# project_Sheet.net
KiCad netlist of a schematic drawn in Altium Designer
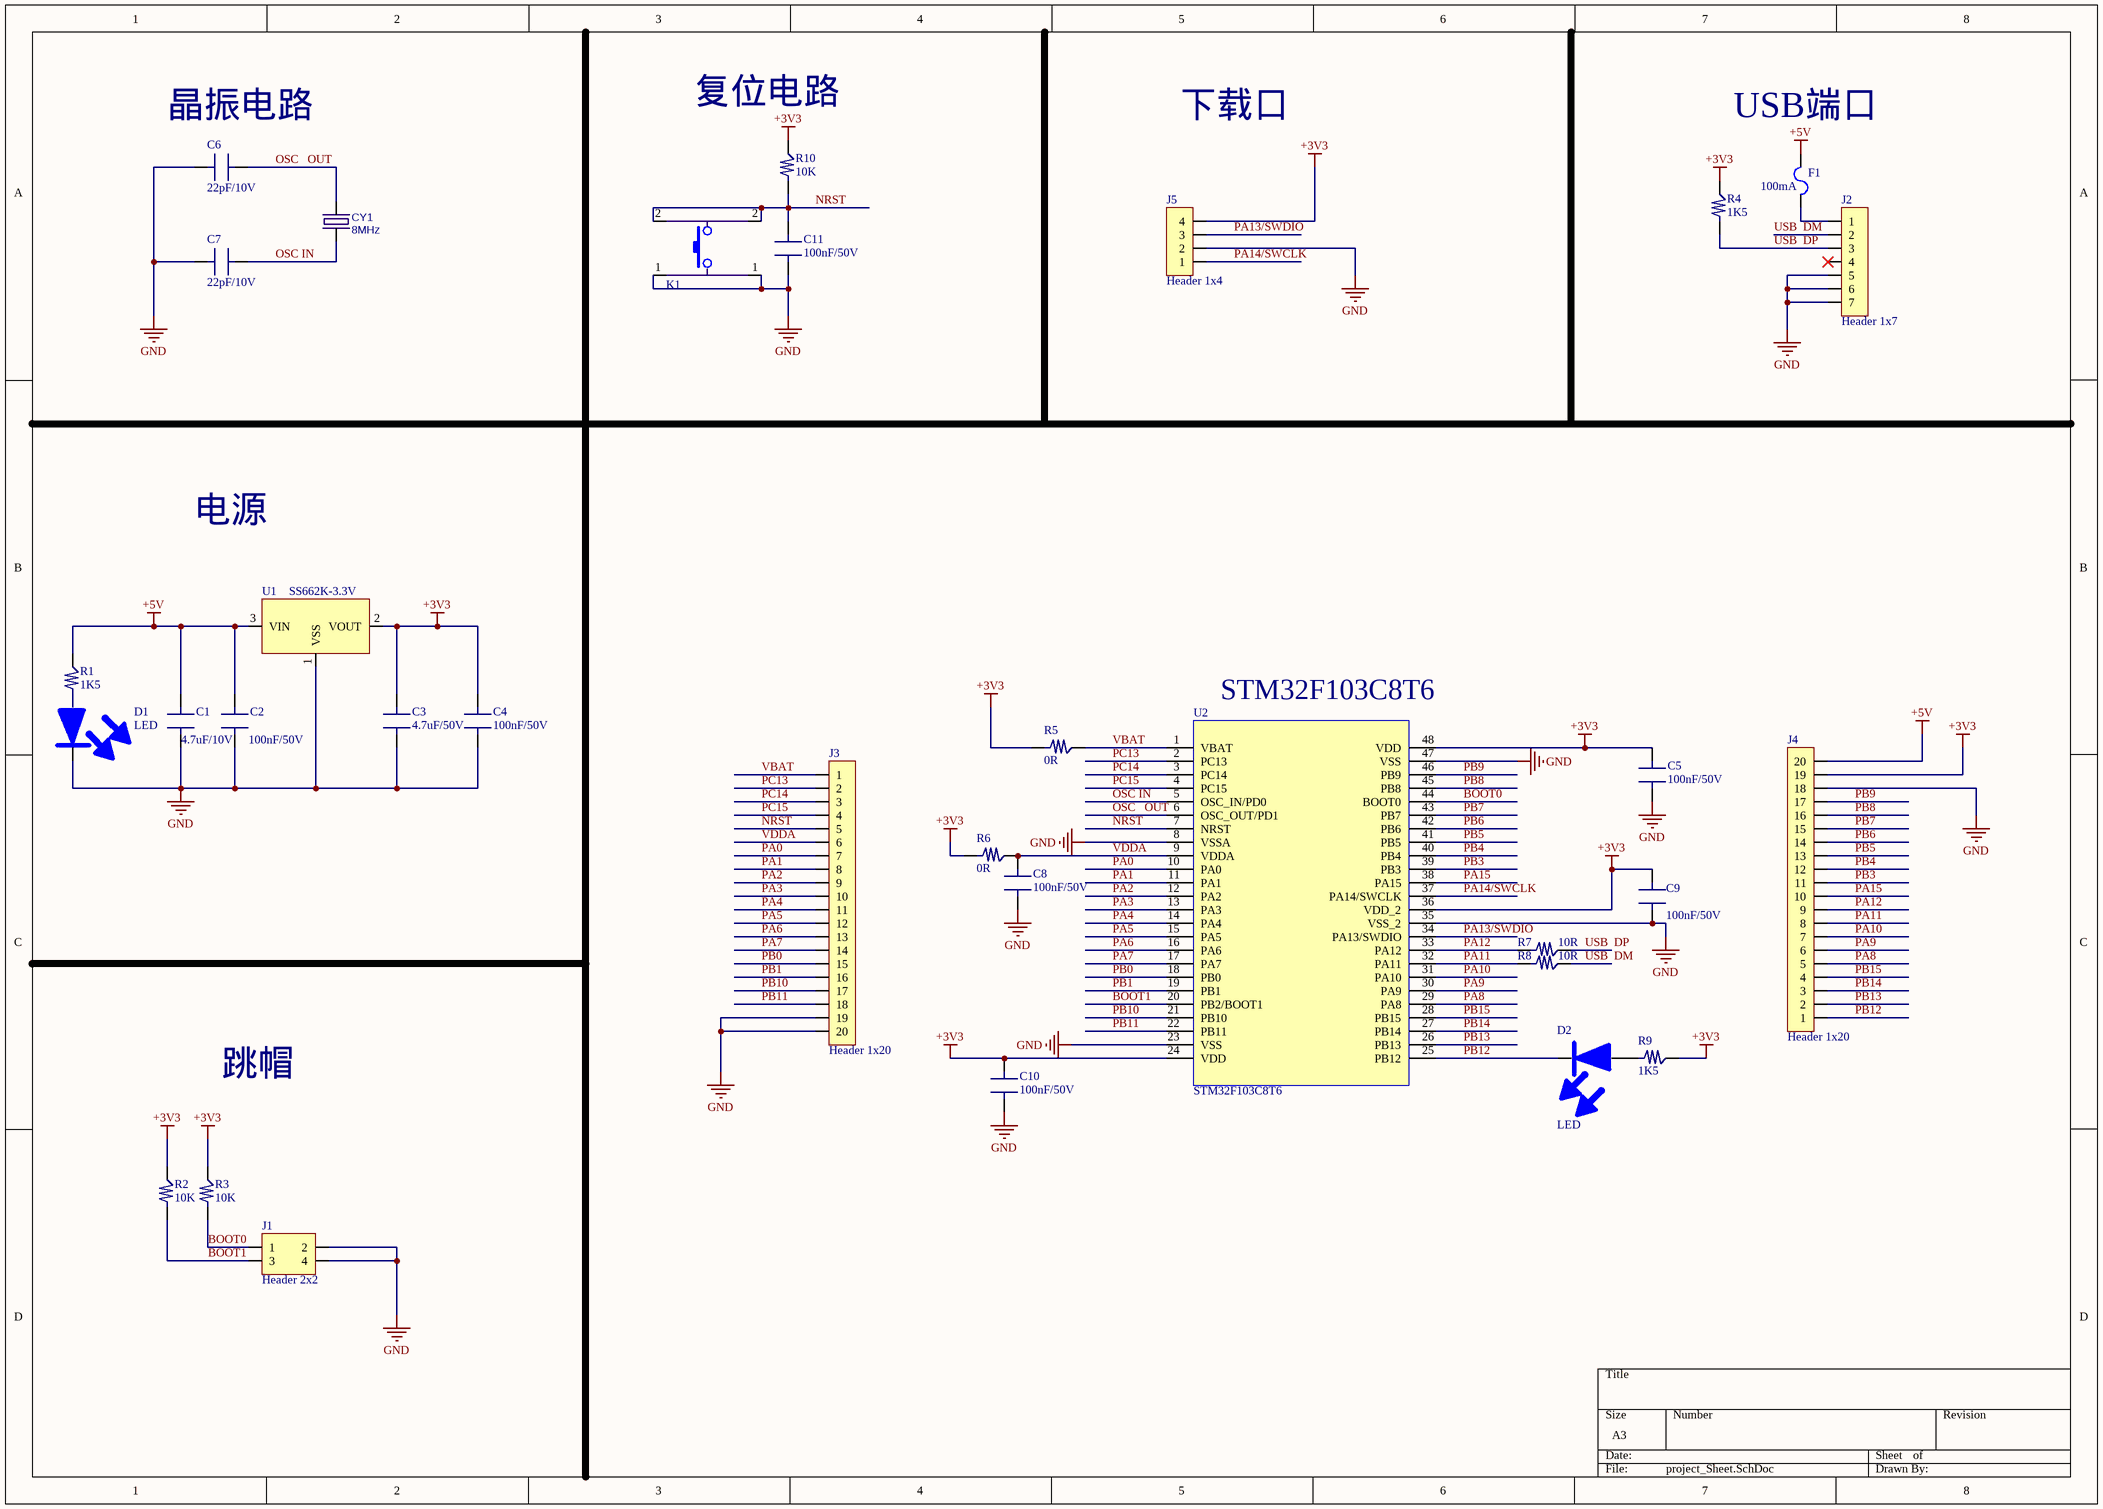
[diagram p0: project_Sheet.SchDoc]

(export (version "E")
  (design (tool "Eeschema 10.0.6"))
  (components
    (comp (ref "C1") (value "4.7uF/10V") (footprint "0603CC") (libsource (lib "F1A") (part "CAP")))
    (comp (ref "C2") (value "100nF/50V") (footprint "0603CC") (libsource (lib "F1A") (part "CAP")))
    (comp (ref "C3") (value "4.7uF/50V") (footprint "0805CC") (libsource (lib "F1A") (part "CAP")))
    (comp (ref "C4") (value "100nF/50V") (footprint "0805CC") (libsource (lib "F1A") (part "CAP")))
    (comp (ref "C5") (value "100nF/50V") (footprint "0603CC") (libsource (lib "F1A") (part "CAP")))
    (comp (ref "C6") (value "22pF/10V") (footprint "0603CC") (libsource (lib "F1A") (part "CAP")))
    (comp (ref "C7") (value "22pF/10V") (footprint "0603CC") (libsource (lib "F1A") (part "CAP")))
    (comp (ref "C8") (value "100nF/50V") (footprint "0603CC") (libsource (lib "F1A") (part "CAP")))
    (comp (ref "C9") (value "100nF/50V") (footprint "0603CC") (libsource (lib "F1A") (part "CAP")))
    (comp (ref "C10") (value "100nF/50V") (footprint "0603CC") (libsource (lib "F1A") (part "CAP")))
    (comp (ref "C11") (value "100nF/50V") (footprint "0603CC") (libsource (lib "F1A") (part "CAP")))
    (comp (ref "CY1")
      (value "8MHz")
      (footprint "HC-49S")
      (description "2pin晶振")
      (libsource (lib "F1A") (part "CY2P"))
    )
    (comp (ref "D1") (value "LED") (footprint "0603LED") (libsource (lib "F1A") (part "LED")))
    (comp (ref "D2") (value "LED") (footprint "0603LED") (libsource (lib "F1A") (part "LED")))
    (comp (ref "F1")
      (value "100mA")
      (footprint "R0805")
      (description "保险丝")
      (libsource (lib "F1A") (part "FUSE"))
    )
    (comp (ref "J1")
      (value "Header 2x2")
      (footprint "HDR2X2")
      (description "双排连接器")
      (libsource (lib "F1A") (part "Header2*2"))
    )
    (comp (ref "J2")
      (value "Header 1x7")
      (footprint "PCBComponent_1")
      (description "单排连接器")
      (libsource (lib "F1A") (part "Header 1x7"))
    )
    (comp (ref "J3")
      (value "Header 1x20")
      (footprint "HDR1X20")
      (description "单排连接器")
      (libsource (lib "") (part "Header 1x20_1"))
    )
    (comp (ref "J4")
      (value "Header 1x20")
      (footprint "HDR1X20")
      (description "单排连接器")
      (libsource (lib "F1A") (part "Header 1x20"))
    )
    (comp (ref "J5")
      (value "Header 1x4")
      (footprint "HDR1X4")
      (description "单排连接器")
      (libsource (lib "F1A") (part "Header 1x4"))
    )
    (comp (ref "K1")
      (value "SW4P")
      (footprint "4.5*4.5*3.8")
      (description "4Pin轻触按键")
      (libsource (lib "F1A") (part "SW4P"))
    )
    (comp (ref "R1")
      (value "1K5")
      (footprint "0603R")
      (description "分立电阻")
      (libsource (lib "F1A") (part "RES"))
    )
    (comp (ref "R2")
      (value "10K")
      (footprint "0603R")
      (description "分立电阻")
      (libsource (lib "F1A") (part "RES"))
    )
    (comp (ref "R3")
      (value "10K")
      (footprint "0603R")
      (description "分立电阻")
      (libsource (lib "F1A") (part "RES"))
    )
    (comp (ref "R4")
      (value "1K5")
      (footprint "0603R")
      (description "分立电阻")
      (libsource (lib "F1A") (part "RES"))
    )
    (comp (ref "R5")
      (value "0R")
      (footprint "0603R")
      (description "分立电阻")
      (libsource (lib "F1A") (part "RES"))
    )
    (comp (ref "R6")
      (value "0R")
      (footprint "0603R")
      (description "分立电阻")
      (libsource (lib "F1A") (part "RES"))
    )
    (comp (ref "R7")
      (value "10R")
      (footprint "0603R")
      (description "分立电阻")
      (libsource (lib "F1A") (part "RES"))
    )
    (comp (ref "R8")
      (value "10R")
      (footprint "0603R")
      (description "分立电阻")
      (libsource (lib "F1A") (part "RES"))
    )
    (comp (ref "R9")
      (value "1K5")
      (footprint "0603R")
      (description "分立电阻")
      (libsource (lib "F1A") (part "RES"))
    )
    (comp (ref "R10")
      (value "10K")
      (footprint "0603R")
      (description "分立电阻")
      (libsource (lib "F1A") (part "RES"))
    )
    (comp (ref "U1") (value "SS662K-3.3V") (footprint "SOT23-JX") (libsource (lib "F1A") (part "SS662K")))
    (comp (ref "U2")
      (value "STM32F103C8T6")
      (footprint "LQFP48")
      (description "STM32单片机")
      (libsource (lib "F1A") (part "STM32F103C8T6"))
    )
  )
  (nets
    (net (code "1") (name "+3V3") (class "Default")
      (node (ref "C10") (pin "2") (pinfunction "2_2") (pintype "passive"))
      (node (ref "C3") (pin "2") (pinfunction "2_2") (pintype "passive"))
      (node (ref "C4") (pin "2") (pinfunction "2_2") (pintype "passive"))
      (node (ref "C5") (pin "2") (pinfunction "2_2") (pintype "passive"))
      (node (ref "C9") (pin "2") (pinfunction "2_2") (pintype "passive"))
      (node (ref "J4") (pin "19") (pinfunction "19_19") (pintype "passive"))
      (node (ref "J5") (pin "4") (pinfunction "4_4") (pintype "passive"))
      (node (ref "R10") (pin "2") (pinfunction "2_2") (pintype "passive"))
      (node (ref "R2") (pin "2") (pinfunction "2_2") (pintype "passive"))
      (node (ref "R3") (pin "2") (pinfunction "2_2") (pintype "passive"))
      (node (ref "R4") (pin "2") (pinfunction "2_2") (pintype "passive"))
      (node (ref "R5") (pin "1") (pinfunction "1_1") (pintype "passive"))
      (node (ref "R6") (pin "1") (pinfunction "1_1") (pintype "passive"))
      (node (ref "R9") (pin "2") (pinfunction "2_2") (pintype "passive"))
      (node (ref "U1") (pin "2") (pinfunction "VOUT_2") (pintype "passive"))
      (node (ref "U2") (pin "24") (pinfunction "VDD_24") (pintype "passive"))
      (node (ref "U2") (pin "36") (pinfunction "VDD_2_36") (pintype "passive"))
      (node (ref "U2") (pin "48") (pinfunction "VDD_48") (pintype "passive"))
    )
    (net (code "2") (name "+5V") (class "Default")
      (node (ref "C1") (pin "2") (pinfunction "2_2") (pintype "passive"))
      (node (ref "C2") (pin "2") (pinfunction "2_2") (pintype "passive"))
      (node (ref "F1") (pin "2") (pinfunction "2_2") (pintype "passive"))
      (node (ref "J4") (pin "20") (pinfunction "20_20") (pintype "passive"))
      (node (ref "R1") (pin "2") (pinfunction "2_2") (pintype "passive"))
      (node (ref "U1") (pin "3") (pinfunction "VIN_3") (pintype "passive"))
    )
    (net (code "3") (name "/BOOT0") (class "Default")
      (node (ref "J1") (pin "1") (pinfunction "1_1") (pintype "passive"))
      (node (ref "R3") (pin "1") (pinfunction "1_1") (pintype "passive"))
      (node (ref "U2") (pin "44") (pinfunction "BOOT0_44") (pintype "passive"))
    )
    (net (code "4") (name "/BOOT1") (class "Default")
      (node (ref "J1") (pin "3") (pinfunction "3_3") (pintype "passive"))
      (node (ref "R2") (pin "1") (pinfunction "1_1") (pintype "passive"))
      (node (ref "U2") (pin "20") (pinfunction "PB2/BOOT1_20") (pintype "passive"))
    )
    (net (code "5") (name "/NRST") (class "Default")
      (node (ref "C11") (pin "2") (pinfunction "2_2") (pintype "passive"))
      (node (ref "J3") (pin "5") (pinfunction "5_5") (pintype "passive"))
      (node (ref "K1") (pin "2") (pinfunction "3_2") (pintype "passive"))
      (node (ref "R10") (pin "1") (pinfunction "1_1") (pintype "passive"))
      (node (ref "U2") (pin "7") (pinfunction "NRST_7") (pintype "passive"))
    )
    (net (code "6") (name "/OSC   OUT") (class "Default")
      (node (ref "C6") (pin "2") (pinfunction "2_2") (pintype "passive"))
      (node (ref "CY1") (pin "2") (pinfunction "2_2") (pintype "passive"))
      (node (ref "U2") (pin "6") (pinfunction "OSC_OUT/PD1_6") (pintype "passive"))
    )
    (net (code "7") (name "/OSC IN") (class "Default")
      (node (ref "C7") (pin "2") (pinfunction "2_2") (pintype "passive"))
      (node (ref "CY1") (pin "1") (pinfunction "1_1") (pintype "passive"))
      (node (ref "U2") (pin "5") (pinfunction "OSC_IN/PD0_5") (pintype "passive"))
    )
    (net (code "8") (name "/PA0") (class "Default")
      (node (ref "J3") (pin "7") (pinfunction "7_7") (pintype "passive"))
      (node (ref "U2") (pin "10") (pinfunction "PA0_10") (pintype "passive"))
    )
    (net (code "9") (name "/PA1") (class "Default")
      (node (ref "J3") (pin "8") (pinfunction "8_8") (pintype "passive"))
      (node (ref "U2") (pin "11") (pinfunction "PA1_11") (pintype "passive"))
    )
    (net (code "10") (name "/PA2") (class "Default")
      (node (ref "J3") (pin "9") (pinfunction "9_9") (pintype "passive"))
      (node (ref "U2") (pin "12") (pinfunction "PA2_12") (pintype "passive"))
    )
    (net (code "11") (name "/PA3") (class "Default")
      (node (ref "J3") (pin "10") (pinfunction "10_10") (pintype "passive"))
      (node (ref "U2") (pin "13") (pinfunction "PA3_13") (pintype "passive"))
    )
    (net (code "12") (name "/PA4") (class "Default")
      (node (ref "J3") (pin "11") (pinfunction "11_11") (pintype "passive"))
      (node (ref "U2") (pin "14") (pinfunction "PA4_14") (pintype "passive"))
    )
    (net (code "13") (name "/PA5") (class "Default")
      (node (ref "J3") (pin "12") (pinfunction "12_12") (pintype "passive"))
      (node (ref "U2") (pin "15") (pinfunction "PA5_15") (pintype "passive"))
    )
    (net (code "14") (name "/PA6") (class "Default")
      (node (ref "J3") (pin "13") (pinfunction "13_13") (pintype "passive"))
      (node (ref "U2") (pin "16") (pinfunction "PA6_16") (pintype "passive"))
    )
    (net (code "15") (name "/PA7") (class "Default")
      (node (ref "J3") (pin "14") (pinfunction "14_14") (pintype "passive"))
      (node (ref "U2") (pin "17") (pinfunction "PA7_17") (pintype "passive"))
    )
    (net (code "16") (name "/PA8") (class "Default")
      (node (ref "J4") (pin "5") (pinfunction "5_5") (pintype "passive"))
      (node (ref "U2") (pin "29") (pinfunction "PA8_29") (pintype "passive"))
    )
    (net (code "17") (name "/PA9") (class "Default")
      (node (ref "J4") (pin "6") (pinfunction "6_6") (pintype "passive"))
      (node (ref "U2") (pin "30") (pinfunction "PA9_30") (pintype "passive"))
    )
    (net (code "18") (name "/PA10") (class "Default")
      (node (ref "J4") (pin "7") (pinfunction "7_7") (pintype "passive"))
      (node (ref "U2") (pin "31") (pinfunction "PA10_31") (pintype "passive"))
    )
    (net (code "19") (name "/PA11") (class "Default")
      (node (ref "J4") (pin "8") (pinfunction "8_8") (pintype "passive"))
      (node (ref "R8") (pin "1") (pinfunction "1_1") (pintype "passive"))
      (node (ref "U2") (pin "32") (pinfunction "PA11_32") (pintype "passive"))
    )
    (net (code "20") (name "/PA12") (class "Default")
      (node (ref "J4") (pin "9") (pinfunction "9_9") (pintype "passive"))
      (node (ref "R7") (pin "1") (pinfunction "1_1") (pintype "passive"))
      (node (ref "U2") (pin "33") (pinfunction "PA12_33") (pintype "passive"))
    )
    (net (code "21") (name "/PA13{slash}SWDIO") (class "Default")
      (node (ref "J5") (pin "3") (pinfunction "3_3") (pintype "passive"))
      (node (ref "U2") (pin "34") (pinfunction "PA13/SWDIO_34") (pintype "passive"))
    )
    (net (code "22") (name "/PA14{slash}SWCLK") (class "Default")
      (node (ref "J5") (pin "1") (pinfunction "1_1") (pintype "passive"))
      (node (ref "U2") (pin "37") (pinfunction "PA14/SWCLK_37") (pintype "passive"))
    )
    (net (code "23") (name "/PA15") (class "Default")
      (node (ref "J4") (pin "10") (pinfunction "10_10") (pintype "passive"))
      (node (ref "U2") (pin "38") (pinfunction "PA15_38") (pintype "passive"))
    )
    (net (code "24") (name "/PB0") (class "Default")
      (node (ref "J3") (pin "15") (pinfunction "15_15") (pintype "passive"))
      (node (ref "U2") (pin "18") (pinfunction "PB0_18") (pintype "passive"))
    )
    (net (code "25") (name "/PB1") (class "Default")
      (node (ref "J3") (pin "16") (pinfunction "16_16") (pintype "passive"))
      (node (ref "U2") (pin "19") (pinfunction "PB1_19") (pintype "passive"))
    )
    (net (code "26") (name "/PB3") (class "Default")
      (node (ref "J4") (pin "11") (pinfunction "11_11") (pintype "passive"))
      (node (ref "U2") (pin "39") (pinfunction "PB3_39") (pintype "passive"))
    )
    (net (code "27") (name "/PB4") (class "Default")
      (node (ref "J4") (pin "12") (pinfunction "12_12") (pintype "passive"))
      (node (ref "U2") (pin "40") (pinfunction "PB4_40") (pintype "passive"))
    )
    (net (code "28") (name "/PB5") (class "Default")
      (node (ref "J4") (pin "13") (pinfunction "13_13") (pintype "passive"))
      (node (ref "U2") (pin "41") (pinfunction "PB5_41") (pintype "passive"))
    )
    (net (code "29") (name "/PB6") (class "Default")
      (node (ref "J4") (pin "14") (pinfunction "14_14") (pintype "passive"))
      (node (ref "U2") (pin "42") (pinfunction "PB6_42") (pintype "passive"))
    )
    (net (code "30") (name "/PB7") (class "Default")
      (node (ref "J4") (pin "15") (pinfunction "15_15") (pintype "passive"))
      (node (ref "U2") (pin "43") (pinfunction "PB7_43") (pintype "passive"))
    )
    (net (code "31") (name "/PB8") (class "Default")
      (node (ref "J4") (pin "16") (pinfunction "16_16") (pintype "passive"))
      (node (ref "U2") (pin "45") (pinfunction "PB8_45") (pintype "passive"))
    )
    (net (code "32") (name "/PB9") (class "Default")
      (node (ref "J4") (pin "17") (pinfunction "17_17") (pintype "passive"))
      (node (ref "U2") (pin "46") (pinfunction "PB9_46") (pintype "passive"))
    )
    (net (code "33") (name "/PB10") (class "Default")
      (node (ref "J3") (pin "17") (pinfunction "17_17") (pintype "passive"))
      (node (ref "U2") (pin "21") (pinfunction "PB10_21") (pintype "passive"))
    )
    (net (code "34") (name "/PB11") (class "Default")
      (node (ref "J3") (pin "18") (pinfunction "18_18") (pintype "passive"))
      (node (ref "U2") (pin "22") (pinfunction "PB11_22") (pintype "passive"))
    )
    (net (code "35") (name "/PB12") (class "Default")
      (node (ref "D2") (pin "2") (pinfunction "2_2") (pintype "passive"))
      (node (ref "J4") (pin "1") (pinfunction "1_1") (pintype "passive"))
      (node (ref "U2") (pin "25") (pinfunction "PB12_25") (pintype "passive"))
    )
    (net (code "36") (name "/PB13") (class "Default")
      (node (ref "J4") (pin "2") (pinfunction "2_2") (pintype "passive"))
      (node (ref "U2") (pin "26") (pinfunction "PB13_26") (pintype "passive"))
    )
    (net (code "37") (name "/PB14") (class "Default")
      (node (ref "J4") (pin "3") (pinfunction "3_3") (pintype "passive"))
      (node (ref "U2") (pin "27") (pinfunction "PB14_27") (pintype "passive"))
    )
    (net (code "38") (name "/PB15") (class "Default")
      (node (ref "J4") (pin "4") (pinfunction "4_4") (pintype "passive"))
      (node (ref "U2") (pin "28") (pinfunction "PB15_28") (pintype "passive"))
    )
    (net (code "39") (name "/PC13") (class "Default")
      (node (ref "J3") (pin "2") (pinfunction "2_2") (pintype "passive"))
      (node (ref "U2") (pin "2") (pinfunction "PC13_2") (pintype "passive"))
    )
    (net (code "40") (name "/PC14") (class "Default")
      (node (ref "J3") (pin "3") (pinfunction "3_3") (pintype "passive"))
      (node (ref "U2") (pin "3") (pinfunction "PC14_3") (pintype "passive"))
    )
    (net (code "41") (name "/PC15") (class "Default")
      (node (ref "J3") (pin "4") (pinfunction "4_4") (pintype "passive"))
      (node (ref "U2") (pin "4") (pinfunction "PC15_4") (pintype "passive"))
    )
    (net (code "42") (name "/USB  DM") (class "Default")
      (node (ref "J2") (pin "2") (pinfunction "2_2") (pintype "passive"))
      (node (ref "R8") (pin "2") (pinfunction "2_2") (pintype "passive"))
    )
    (net (code "43") (name "/USB  DP") (class "Default")
      (node (ref "J2") (pin "3") (pinfunction "3_3") (pintype "passive"))
      (node (ref "R4") (pin "1") (pinfunction "1_1") (pintype "passive"))
      (node (ref "R7") (pin "2") (pinfunction "2_2") (pintype "passive"))
    )
    (net (code "44") (name "/VBAT") (class "Default")
      (node (ref "J3") (pin "1") (pinfunction "1_1") (pintype "passive"))
      (node (ref "R5") (pin "2") (pinfunction "2_2") (pintype "passive"))
      (node (ref "U2") (pin "1") (pinfunction "VBAT_1") (pintype "passive"))
    )
    (net (code "45") (name "/VDDA") (class "Default")
      (node (ref "C8") (pin "2") (pinfunction "2_2") (pintype "passive"))
      (node (ref "J3") (pin "6") (pinfunction "6_6") (pintype "passive"))
      (node (ref "R6") (pin "2") (pinfunction "2_2") (pintype "passive"))
      (node (ref "U2") (pin "9") (pinfunction "VDDA_9") (pintype "passive"))
    )
    (net (code "46") (name "GND") (class "Default")
      (node (ref "C1") (pin "1") (pinfunction "1_1") (pintype "passive"))
      (node (ref "C10") (pin "1") (pinfunction "1_1") (pintype "passive"))
      (node (ref "C11") (pin "1") (pinfunction "1_1") (pintype "passive"))
      (node (ref "C2") (pin "1") (pinfunction "1_1") (pintype "passive"))
      (node (ref "C3") (pin "1") (pinfunction "1_1") (pintype "passive"))
      (node (ref "C4") (pin "1") (pinfunction "1_1") (pintype "passive"))
      (node (ref "C5") (pin "1") (pinfunction "1_1") (pintype "passive"))
      (node (ref "C6") (pin "1") (pinfunction "1_1") (pintype "passive"))
      (node (ref "C7") (pin "1") (pinfunction "1_1") (pintype "passive"))
      (node (ref "C8") (pin "1") (pinfunction "1_1") (pintype "passive"))
      (node (ref "C9") (pin "1") (pinfunction "1_1") (pintype "passive"))
      (node (ref "D1") (pin "2") (pinfunction "2_2") (pintype "passive"))
      (node (ref "J1") (pin "2") (pinfunction "2_2") (pintype "passive"))
      (node (ref "J1") (pin "4") (pinfunction "4_4") (pintype "passive"))
      (node (ref "J2") (pin "5") (pinfunction "5_5") (pintype "passive"))
      (node (ref "J2") (pin "6") (pinfunction "6_6") (pintype "passive"))
      (node (ref "J2") (pin "7") (pinfunction "7_7") (pintype "passive"))
      (node (ref "J3") (pin "19") (pinfunction "19_19") (pintype "passive"))
      (node (ref "J3") (pin "20") (pinfunction "20_20") (pintype "passive"))
      (node (ref "J4") (pin "18") (pinfunction "18_18") (pintype "passive"))
      (node (ref "J5") (pin "2") (pinfunction "2_2") (pintype "passive"))
      (node (ref "K1") (pin "1") (pinfunction "2_1") (pintype "passive"))
      (node (ref "U1") (pin "1") (pinfunction "VSS_1") (pintype "passive"))
      (node (ref "U2") (pin "23") (pinfunction "VSS_23") (pintype "passive"))
      (node (ref "U2") (pin "35") (pinfunction "VSS_2_35") (pintype "passive"))
      (node (ref "U2") (pin "47") (pinfunction "VSS_47") (pintype "passive"))
      (node (ref "U2") (pin "8") (pinfunction "VSSA_8") (pintype "passive"))
    )
    (net (code "47") (name "Net-(D1-Pad1)") (class "Default")
      (node (ref "D1") (pin "1") (pinfunction "1_1") (pintype "passive"))
      (node (ref "R1") (pin "1") (pinfunction "1_1") (pintype "passive"))
    )
    (net (code "48") (name "Net-(D2-Pad1)") (class "Default")
      (node (ref "D2") (pin "1") (pinfunction "1_1") (pintype "passive"))
      (node (ref "R9") (pin "1") (pinfunction "1_1") (pintype "passive"))
    )
    (net (code "49") (name "Net-(F1-Pad1)") (class "Default")
      (node (ref "F1") (pin "1") (pinfunction "1_1") (pintype "passive"))
      (node (ref "J2") (pin "1") (pinfunction "1_1") (pintype "passive"))
    )
    (net (code "50") (name "unconnected-(J2-Pad4)") (class "Default")
      (node (ref "J2") (pin "4") (pinfunction "4_4") (pintype "passive+no_connect"))
    )
  )
)
